# SCH_SEEK-993-001_v1_00.net
KiCad netlist of a schematic drawn in EasyEDA
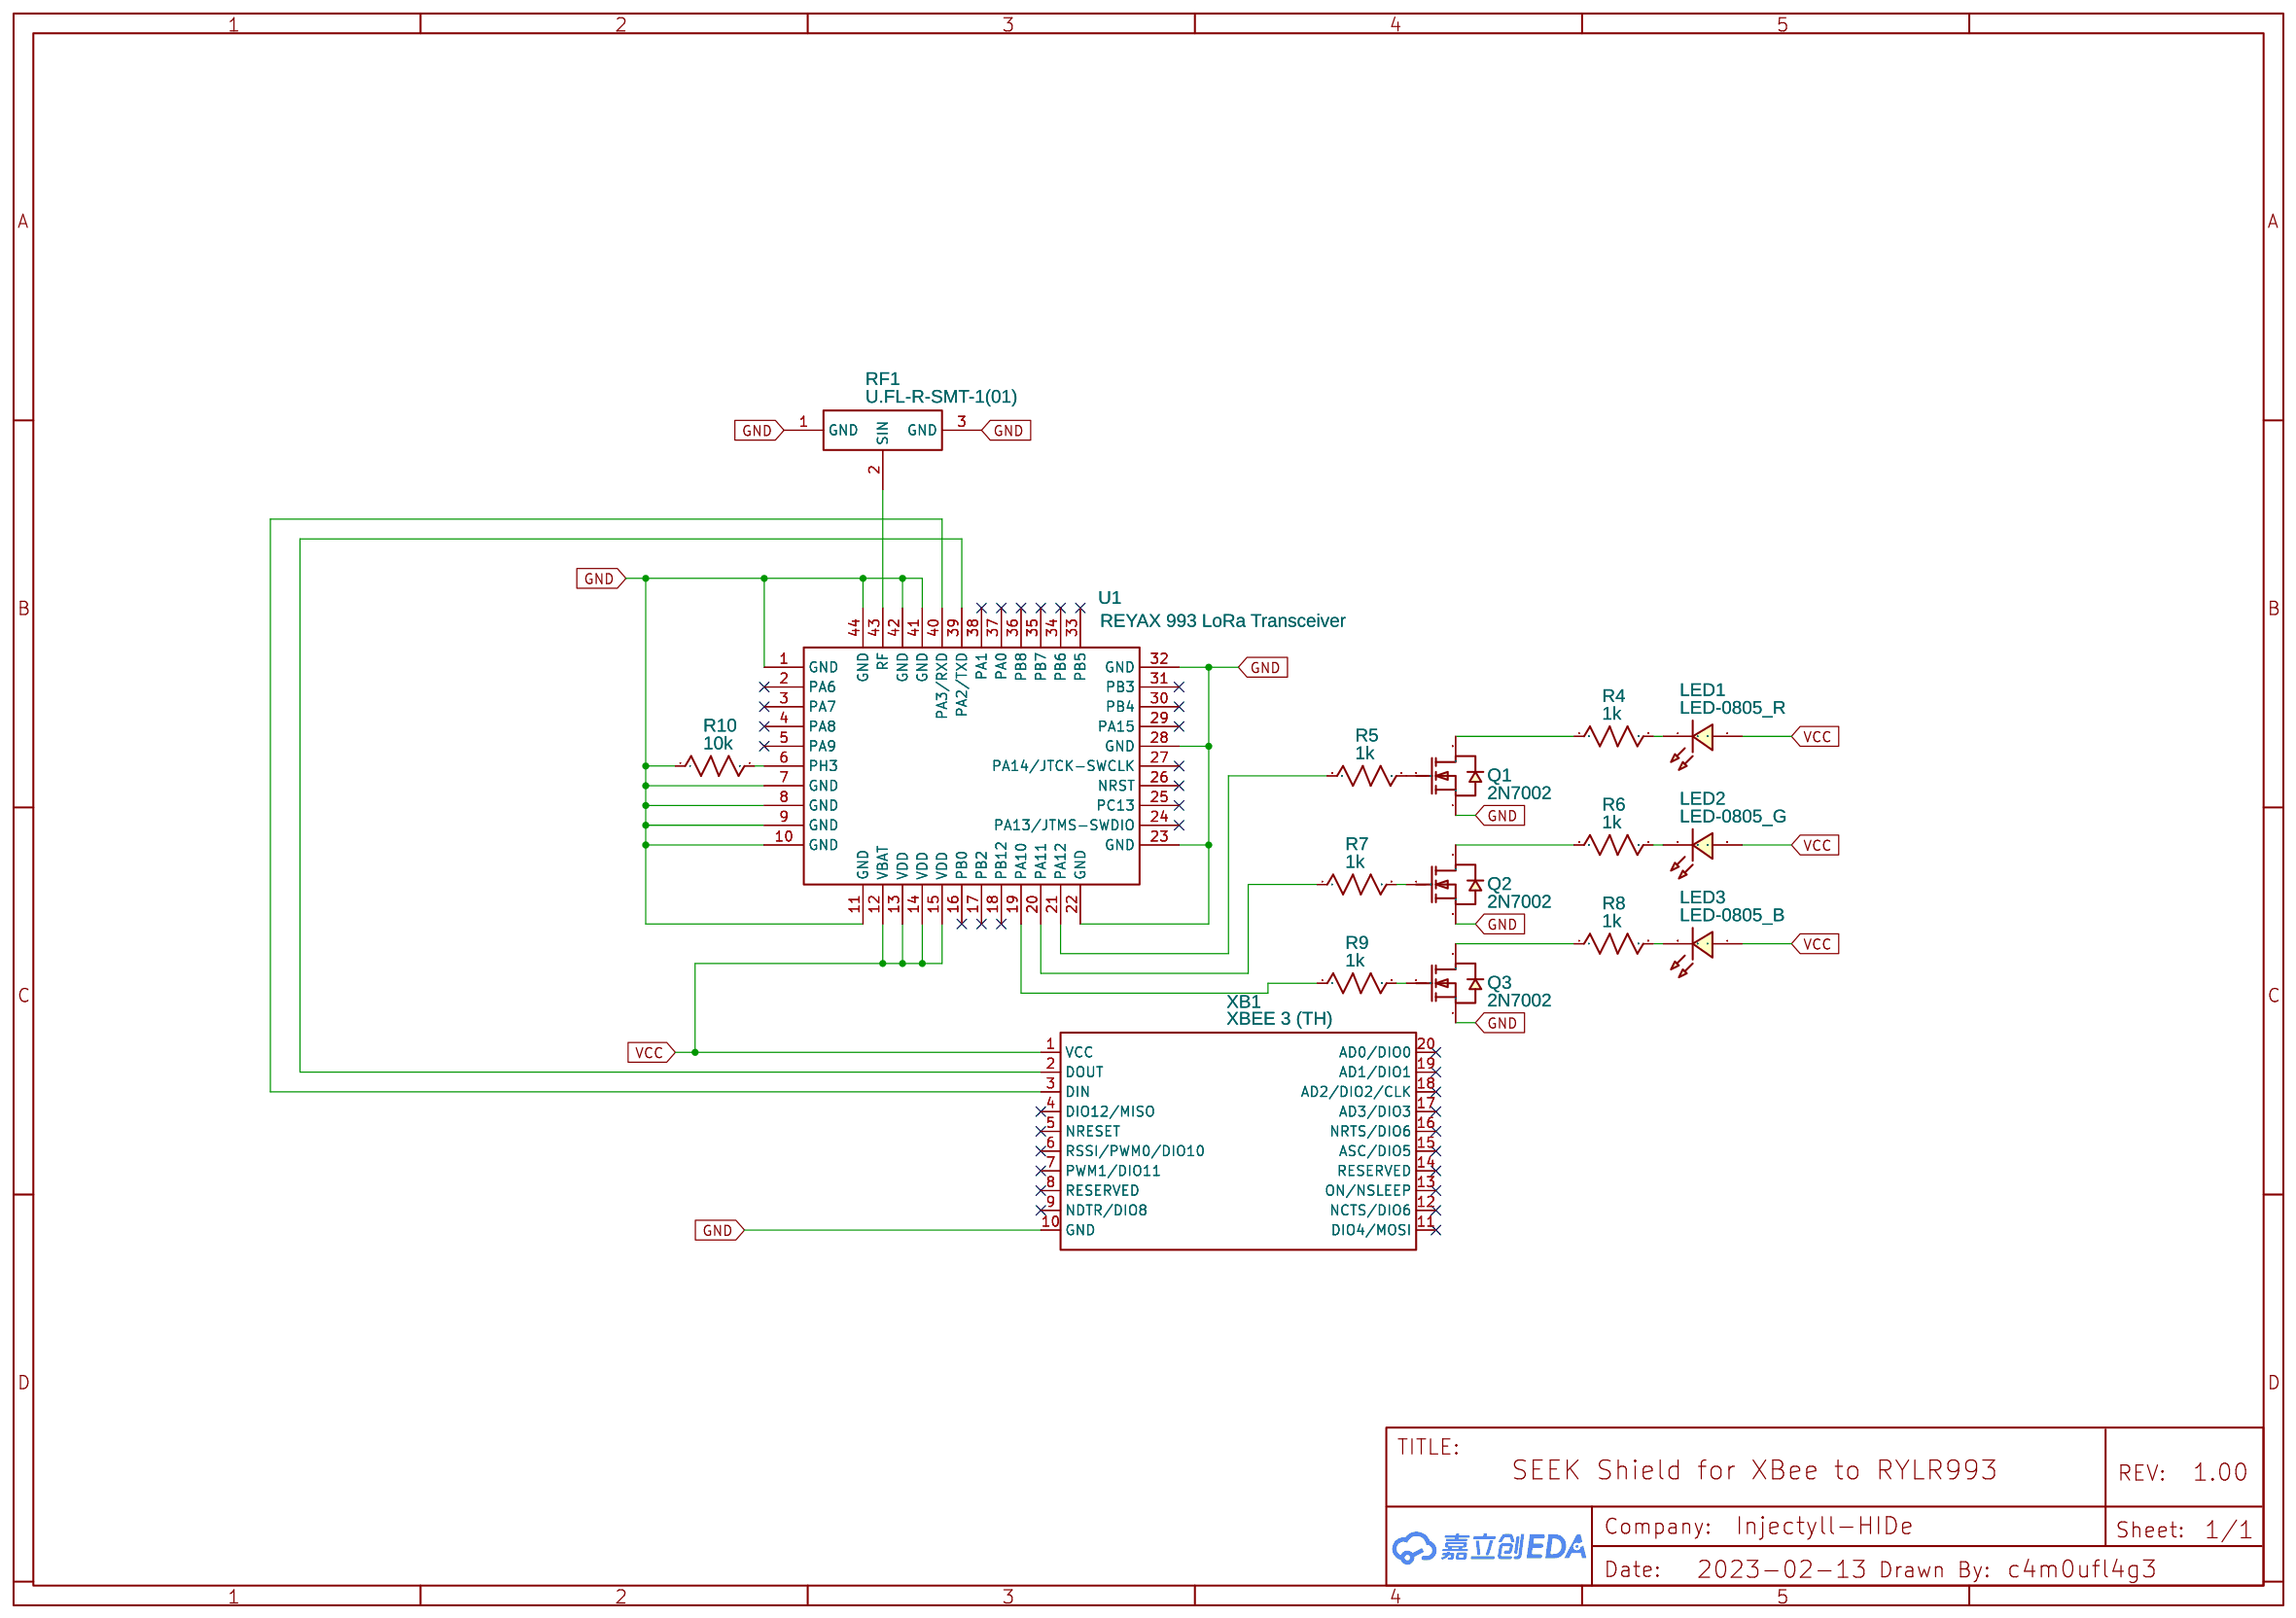
[diagram p0: schematic sheet]

(export (version "E")
  (design (tool "Eeschema 10.0.6"))
  (components
    (comp (ref "LED1")
      (value "LED-0805_R")
      (fields
        (field (name "BOM_Manufacturer Part") "17-21SURC/S530-A3/TR8")
        (field (name "BOM_Supplier Part") "C72037")
      )
      (libsource (lib "") (part "LED-0805_R"))
    )
    (comp (ref "LED2")
      (value "LED-0805_G")
      (fields (field (name "BOM_Manufacturer Part") "NCD0805G1") (field (name "BOM_Supplier Part") "C84260"))
      (libsource (lib "") (part "LED-0805_G"))
    )
    (comp (ref "LED3")
      (value "LED-0805_B")
      (fields
        (field (name "BOM_Manufacturer Part") "D-B080508B1-KS2")
        (field (name "BOM_Supplier Part") "C108412")
      )
      (libsource (lib "") (part "LED-0805_B"))
    )
    (comp (ref "Q1")
      (value "2N7002")
      (fields (field (name "BOM_Manufacturer Part") "2N7002,215") (field (name "BOM_Supplier Part") "C65189"))
      (libsource (lib "") (part "2N7002"))
    )
    (comp (ref "Q2")
      (value "2N7002")
      (fields (field (name "BOM_Manufacturer Part") "2N7002,215") (field (name "BOM_Supplier Part") "C65189"))
      (libsource (lib "") (part "2N7002"))
    )
    (comp (ref "Q3")
      (value "2N7002")
      (fields (field (name "BOM_Manufacturer Part") "2N7002,215") (field (name "BOM_Supplier Part") "C65189"))
      (libsource (lib "") (part "2N7002"))
    )
    (comp (ref "R4") (value "1k") (libsource (lib "") (part "R_0402_US")))
    (comp (ref "R5") (value "1k") (libsource (lib "") (part "R_0402_US")))
    (comp (ref "R6") (value "1k") (libsource (lib "") (part "R_0402_US")))
    (comp (ref "R7") (value "1k") (libsource (lib "") (part "R_0402_US")))
    (comp (ref "R8") (value "1k") (libsource (lib "") (part "R_0402_US")))
    (comp (ref "R9") (value "1k") (libsource (lib "") (part "R_0402_US")))
    (comp (ref "R10") (value "10k") (libsource (lib "") (part "R_0402_US")))
    (comp (ref "RF1")
      (value "U.FL-R-SMT-1(01)")
      (fields (field (name "BOM_Supplier Part") "C598199"))
      (libsource (lib "") (part "U.FL-R-SMT-1(01)"))
    )
    (comp (ref "U1")
      (value "REYAX 993 LoRa Transceiver")
      (fields (field (name "BOM_Manufacturer Part") "RYLR993"))
      (libsource (lib "") (part "REYAX 993 LoRa Transceiver"))
    )
    (comp (ref "XB1") (value "XBEE 3 (TH)") (libsource (lib "") (part "XBEE 3 (TH)")))
  )
  (nets
    (net (code "1") (name "GND") (class "Default")
      (node (ref "Q1") (pin "2") (pinfunction "S_2") (pintype "unspecified"))
      (node (ref "Q2") (pin "2") (pinfunction "S_2") (pintype "unspecified"))
      (node (ref "Q3") (pin "2") (pinfunction "S_2") (pintype "unspecified"))
      (node (ref "R10") (pin "1") (pinfunction "1_1") (pintype "unspecified"))
      (node (ref "RF1") (pin "1") (pinfunction "GND_1") (pintype "unspecified"))
      (node (ref "RF1") (pin "3") (pinfunction "GND_3") (pintype "unspecified"))
      (node (ref "U1") (pin "1") (pinfunction "GND_1") (pintype "unspecified"))
      (node (ref "U1") (pin "10") (pinfunction "GND_10") (pintype "unspecified"))
      (node (ref "U1") (pin "11") (pinfunction "GND_11") (pintype "unspecified"))
      (node (ref "U1") (pin "22") (pinfunction "GND_22") (pintype "unspecified"))
      (node (ref "U1") (pin "23") (pinfunction "GND_23") (pintype "unspecified"))
      (node (ref "U1") (pin "28") (pinfunction "GND_28") (pintype "unspecified"))
      (node (ref "U1") (pin "32") (pinfunction "GND_32") (pintype "unspecified"))
      (node (ref "U1") (pin "41") (pinfunction "GND_41") (pintype "unspecified"))
      (node (ref "U1") (pin "42") (pinfunction "GND_42") (pintype "unspecified"))
      (node (ref "U1") (pin "44") (pinfunction "GND_44") (pintype "unspecified"))
      (node (ref "U1") (pin "7") (pinfunction "GND_7") (pintype "unspecified"))
      (node (ref "U1") (pin "8") (pinfunction "GND_8") (pintype "unspecified"))
      (node (ref "U1") (pin "9") (pinfunction "GND_9") (pintype "unspecified"))
      (node (ref "XB1") (pin "10") (pinfunction "GND_10") (pintype "unspecified"))
    )
    (net (code "2") (name "Net-(LED1-Pad2)") (class "Default")
      (node (ref "LED1") (pin "2") (pinfunction "2_2") (pintype "unspecified"))
      (node (ref "R4") (pin "2") (pinfunction "2_2") (pintype "unspecified"))
    )
    (net (code "3") (name "Net-(LED2-Pad2)") (class "Default")
      (node (ref "LED2") (pin "2") (pinfunction "2_2") (pintype "unspecified"))
      (node (ref "R6") (pin "2") (pinfunction "2_2") (pintype "unspecified"))
    )
    (net (code "4") (name "Net-(LED3-Pad2)") (class "Default")
      (node (ref "LED3") (pin "2") (pinfunction "2_2") (pintype "unspecified"))
      (node (ref "R8") (pin "2") (pinfunction "2_2") (pintype "unspecified"))
    )
    (net (code "5") (name "Net-(Q1-D)") (class "Default")
      (node (ref "Q1") (pin "3") (pinfunction "D_3") (pintype "unspecified"))
      (node (ref "R4") (pin "1") (pinfunction "1_1") (pintype "unspecified"))
    )
    (net (code "6") (name "Net-(Q1-G)") (class "Default")
      (node (ref "Q1") (pin "1") (pinfunction "G_1") (pintype "unspecified"))
      (node (ref "R5") (pin "2") (pinfunction "2_2") (pintype "unspecified"))
    )
    (net (code "7") (name "Net-(Q2-D)") (class "Default")
      (node (ref "Q2") (pin "3") (pinfunction "D_3") (pintype "unspecified"))
      (node (ref "R6") (pin "1") (pinfunction "1_1") (pintype "unspecified"))
    )
    (net (code "8") (name "Net-(Q2-G)") (class "Default")
      (node (ref "Q2") (pin "1") (pinfunction "G_1") (pintype "unspecified"))
      (node (ref "R7") (pin "2") (pinfunction "2_2") (pintype "unspecified"))
    )
    (net (code "9") (name "Net-(Q3-D)") (class "Default")
      (node (ref "Q3") (pin "3") (pinfunction "D_3") (pintype "unspecified"))
      (node (ref "R8") (pin "1") (pinfunction "1_1") (pintype "unspecified"))
    )
    (net (code "10") (name "Net-(Q3-G)") (class "Default")
      (node (ref "Q3") (pin "1") (pinfunction "G_1") (pintype "unspecified"))
      (node (ref "R9") (pin "2") (pinfunction "2_2") (pintype "unspecified"))
    )
    (net (code "11") (name "Net-(RF1-SIN)") (class "Default")
      (node (ref "RF1") (pin "2") (pinfunction "SIN_2") (pintype "unspecified"))
      (node (ref "U1") (pin "43") (pinfunction "RF_43") (pintype "unspecified"))
    )
    (net (code "12") (name "Net-(U1-PA2{slash}TXD)") (class "Default")
      (node (ref "U1") (pin "39") (pinfunction "PA2/TXD_39") (pintype "unspecified"))
      (node (ref "XB1") (pin "2") (pinfunction "DOUT_2") (pintype "unspecified"))
    )
    (net (code "13") (name "Net-(U1-PA3{slash}RXD)") (class "Default")
      (node (ref "U1") (pin "40") (pinfunction "PA3/RXD_40") (pintype "unspecified"))
      (node (ref "XB1") (pin "3") (pinfunction "DIN_3") (pintype "unspecified"))
    )
    (net (code "14") (name "Net-(U1-PA10)") (class "Default")
      (node (ref "R9") (pin "1") (pinfunction "1_1") (pintype "unspecified"))
      (node (ref "U1") (pin "19") (pinfunction "PA10_19") (pintype "unspecified"))
    )
    (net (code "15") (name "Net-(U1-PA11)") (class "Default")
      (node (ref "R7") (pin "1") (pinfunction "1_1") (pintype "unspecified"))
      (node (ref "U1") (pin "20") (pinfunction "PA11_20") (pintype "unspecified"))
    )
    (net (code "16") (name "Net-(U1-PA12)") (class "Default")
      (node (ref "R5") (pin "1") (pinfunction "1_1") (pintype "unspecified"))
      (node (ref "U1") (pin "21") (pinfunction "PA12_21") (pintype "unspecified"))
    )
    (net (code "17") (name "Net-(U1-PH3)") (class "Default")
      (node (ref "R10") (pin "2") (pinfunction "2_2") (pintype "unspecified"))
      (node (ref "U1") (pin "6") (pinfunction "PH3_6") (pintype "unspecified"))
    )
    (net (code "18") (name "VCC") (class "Default")
      (node (ref "LED1") (pin "1") (pinfunction "1_1") (pintype "unspecified"))
      (node (ref "LED2") (pin "1") (pinfunction "1_1") (pintype "unspecified"))
      (node (ref "LED3") (pin "1") (pinfunction "1_1") (pintype "unspecified"))
      (node (ref "U1") (pin "12") (pinfunction "VBAT_12") (pintype "unspecified"))
      (node (ref "U1") (pin "13") (pinfunction "VDD_13") (pintype "unspecified"))
      (node (ref "U1") (pin "14") (pinfunction "VDD_14") (pintype "unspecified"))
      (node (ref "U1") (pin "15") (pinfunction "VDD_15") (pintype "unspecified"))
      (node (ref "XB1") (pin "1") (pinfunction "VCC_1") (pintype "unspecified"))
    )
    (net (code "19") (name "unconnected-(U1-NRST-Pad26)") (class "Default")
      (node (ref "U1") (pin "26") (pinfunction "NRST_26") (pintype "unspecified+no_connect"))
    )
    (net (code "20") (name "unconnected-(U1-PA0-Pad37)") (class "Default")
      (node (ref "U1") (pin "37") (pinfunction "PA0_37") (pintype "unspecified+no_connect"))
    )
    (net (code "21") (name "unconnected-(U1-PA1-Pad38)") (class "Default")
      (node (ref "U1") (pin "38") (pinfunction "PA1_38") (pintype "unspecified+no_connect"))
    )
    (net (code "22") (name "unconnected-(U1-PA6-Pad2)") (class "Default")
      (node (ref "U1") (pin "2") (pinfunction "PA6_2") (pintype "unspecified+no_connect"))
    )
    (net (code "23") (name "unconnected-(U1-PA7-Pad3)") (class "Default")
      (node (ref "U1") (pin "3") (pinfunction "PA7_3") (pintype "unspecified+no_connect"))
    )
    (net (code "24") (name "unconnected-(U1-PA8-Pad4)") (class "Default")
      (node (ref "U1") (pin "4") (pinfunction "PA8_4") (pintype "unspecified+no_connect"))
    )
    (net (code "25") (name "unconnected-(U1-PA9-Pad5)") (class "Default")
      (node (ref "U1") (pin "5") (pinfunction "PA9_5") (pintype "unspecified+no_connect"))
    )
    (net (code "26") (name "unconnected-(U1-PA13{slash}JTMS-SWDIO-Pad24)") (class "Default")
      (node (ref "U1") (pin "24") (pinfunction "PA13/JTMS-SWDIO_24") (pintype "unspecified+no_connect"))
    )
    (net (code "27") (name "unconnected-(U1-PA14{slash}JTCK-SWCLK-Pad27)") (class "Default")
      (node (ref "U1") (pin "27") (pinfunction "PA14/JTCK-SWCLK_27") (pintype "unspecified+no_connect"))
    )
    (net (code "28") (name "unconnected-(U1-PA15-Pad29)") (class "Default")
      (node (ref "U1") (pin "29") (pinfunction "PA15_29") (pintype "unspecified+no_connect"))
    )
    (net (code "29") (name "unconnected-(U1-PB0-Pad16)") (class "Default")
      (node (ref "U1") (pin "16") (pinfunction "PB0_16") (pintype "unspecified+no_connect"))
    )
    (net (code "30") (name "unconnected-(U1-PB2-Pad17)") (class "Default")
      (node (ref "U1") (pin "17") (pinfunction "PB2_17") (pintype "unspecified+no_connect"))
    )
    (net (code "31") (name "unconnected-(U1-PB3-Pad31)") (class "Default")
      (node (ref "U1") (pin "31") (pinfunction "PB3_31") (pintype "unspecified+no_connect"))
    )
    (net (code "32") (name "unconnected-(U1-PB4-Pad30)") (class "Default")
      (node (ref "U1") (pin "30") (pinfunction "PB4_30") (pintype "unspecified+no_connect"))
    )
    (net (code "33") (name "unconnected-(U1-PB5-Pad33)") (class "Default")
      (node (ref "U1") (pin "33") (pinfunction "PB5_33") (pintype "unspecified+no_connect"))
    )
    (net (code "34") (name "unconnected-(U1-PB6-Pad34)") (class "Default")
      (node (ref "U1") (pin "34") (pinfunction "PB6_34") (pintype "unspecified+no_connect"))
    )
    (net (code "35") (name "unconnected-(U1-PB7-Pad35)") (class "Default")
      (node (ref "U1") (pin "35") (pinfunction "PB7_35") (pintype "unspecified+no_connect"))
    )
    (net (code "36") (name "unconnected-(U1-PB8-Pad36)") (class "Default")
      (node (ref "U1") (pin "36") (pinfunction "PB8_36") (pintype "unspecified+no_connect"))
    )
    (net (code "37") (name "unconnected-(U1-PB12-Pad18)") (class "Default")
      (node (ref "U1") (pin "18") (pinfunction "PB12_18") (pintype "unspecified+no_connect"))
    )
    (net (code "38") (name "unconnected-(U1-PC13-Pad25)") (class "Default")
      (node (ref "U1") (pin "25") (pinfunction "PC13_25") (pintype "unspecified+no_connect"))
    )
    (net (code "39") (name "unconnected-(XB1-AD0{slash}DIO0-Pad20)") (class "Default")
      (node (ref "XB1") (pin "20") (pinfunction "AD0/DIO0_20") (pintype "unspecified+no_connect"))
    )
    (net (code "40") (name "unconnected-(XB1-AD1{slash}DIO1-Pad19)") (class "Default")
      (node (ref "XB1") (pin "19") (pinfunction "AD1/DIO1_19") (pintype "unspecified+no_connect"))
    )
    (net (code "41") (name "unconnected-(XB1-AD2{slash}DIO2{slash}CLK-Pad18)") (class "Default")
      (node (ref "XB1") (pin "18") (pinfunction "AD2/DIO2/CLK_18") (pintype "unspecified+no_connect"))
    )
    (net (code "42") (name "unconnected-(XB1-AD3{slash}DIO3-Pad17)") (class "Default")
      (node (ref "XB1") (pin "17") (pinfunction "AD3/DIO3_17") (pintype "unspecified+no_connect"))
    )
    (net (code "43") (name "unconnected-(XB1-ASC{slash}DIO5-Pad15)") (class "Default")
      (node (ref "XB1") (pin "15") (pinfunction "ASC/DIO5_15") (pintype "unspecified+no_connect"))
    )
    (net (code "44") (name "unconnected-(XB1-DIO4{slash}MOSI-Pad11)") (class "Default")
      (node (ref "XB1") (pin "11") (pinfunction "DIO4/MOSI_11") (pintype "unspecified+no_connect"))
    )
    (net (code "45") (name "unconnected-(XB1-DIO12{slash}MISO-Pad4)") (class "Default")
      (node (ref "XB1") (pin "4") (pinfunction "DIO12/MISO_4") (pintype "unspecified+no_connect"))
    )
    (net (code "46") (name "unconnected-(XB1-NCTS{slash}DIO6-Pad12)") (class "Default")
      (node (ref "XB1") (pin "12") (pinfunction "NCTS/DIO6_12") (pintype "unspecified+no_connect"))
    )
    (net (code "47") (name "unconnected-(XB1-NDTR{slash}DIO8-Pad9)") (class "Default")
      (node (ref "XB1") (pin "9") (pinfunction "NDTR/DIO8_9") (pintype "unspecified+no_connect"))
    )
    (net (code "48") (name "unconnected-(XB1-NRESET-Pad5)") (class "Default")
      (node (ref "XB1") (pin "5") (pinfunction "NRESET_5") (pintype "unspecified+no_connect"))
    )
    (net (code "49") (name "unconnected-(XB1-NRTS{slash}DIO6-Pad16)") (class "Default")
      (node (ref "XB1") (pin "16") (pinfunction "NRTS/DIO6_16") (pintype "unspecified+no_connect"))
    )
    (net (code "50") (name "unconnected-(XB1-ON{slash}NSLEEP-Pad13)") (class "Default")
      (node (ref "XB1") (pin "13") (pinfunction "ON/NSLEEP_13") (pintype "unspecified+no_connect"))
    )
    (net (code "51") (name "unconnected-(XB1-PWM1{slash}DIO11-Pad7)") (class "Default")
      (node (ref "XB1") (pin "7") (pinfunction "PWM1/DIO11_7") (pintype "unspecified+no_connect"))
    )
    (net (code "52") (name "unconnected-(XB1-RESERVED-Pad8)") (class "Default")
      (node (ref "XB1") (pin "8") (pinfunction "RESERVED_8") (pintype "unspecified+no_connect"))
    )
    (net (code "53") (name "unconnected-(XB1-RESERVED-Pad14)") (class "Default")
      (node (ref "XB1") (pin "14") (pinfunction "RESERVED_14") (pintype "unspecified+no_connect"))
    )
    (net (code "54") (name "unconnected-(XB1-RSSI{slash}PWM0{slash}DIO10-Pad6)") (class "Default")
      (node (ref "XB1") (pin "6") (pinfunction "RSSI/PWM0/DIO10_6") (pintype "unspecified+no_connect"))
    )
  )
)
